# ALight.net
KiCad netlist of a schematic drawn in Altium Designer
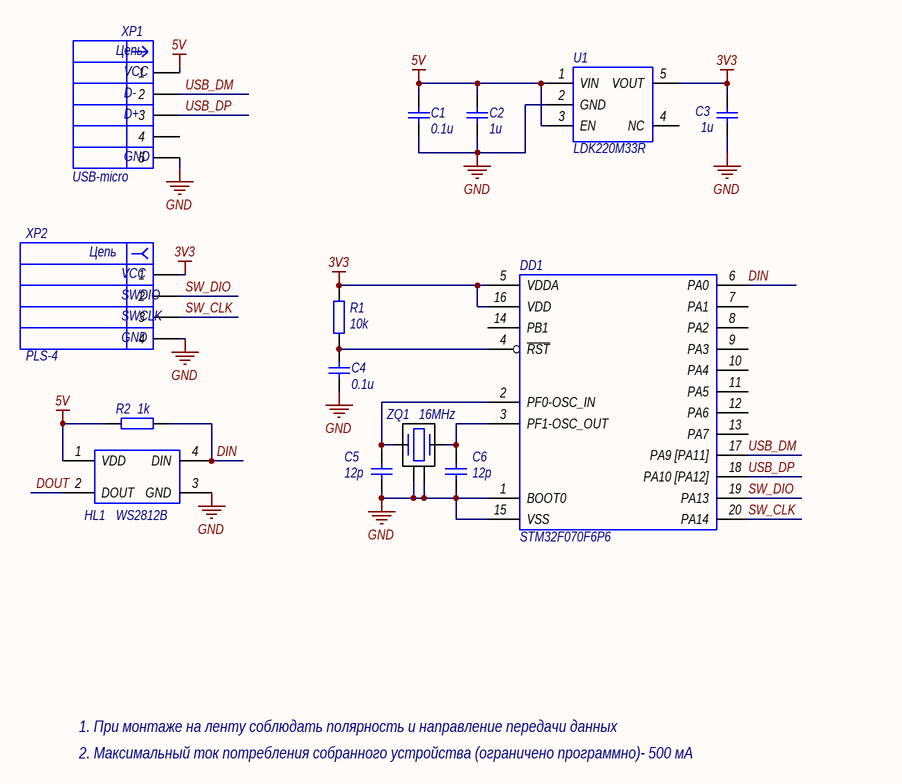
[diagram p0: ALight.SchDoc]

(export (version "E")
  (design (tool "Eeschema 10.0.6"))
  (components
    (comp (ref "C1")
      (value "0.1u")
      (footprint "KDI:CAPACITOR 0603")
      (description "Capacitor")
      (libsource (lib "KDI") (part "SMD-CAP"))
    )
    (comp (ref "C2")
      (value "1u")
      (footprint "KDI:CAPACITOR 0603")
      (description "Capacitor")
      (libsource (lib "KDI") (part "SMD-CAP"))
    )
    (comp (ref "C3")
      (value "1u")
      (footprint "KDI:CAPACITOR 0603")
      (description "Capacitor")
      (libsource (lib "KDI") (part "SMD-CAP"))
    )
    (comp (ref "C4")
      (value "0.1u")
      (footprint "KDI:CAPACITOR 0603")
      (description "Capacitor")
      (libsource (lib "KDI") (part "SMD-CAP"))
    )
    (comp (ref "C5")
      (value "12p")
      (footprint "KDI:CAPACITOR 0603")
      (description "Capacitor")
      (libsource (lib "KDI") (part "SMD-CAP"))
    )
    (comp (ref "C6")
      (value "12p")
      (footprint "KDI:CAPACITOR 0603")
      (description "Capacitor")
      (libsource (lib "KDI") (part "SMD-CAP"))
    )
    (comp (ref "DD1")
      (value "STM32F070F6P6")
      (footprint "TSOP-20")
      (description "Controller")
      (libsource (lib "KDI") (part "STM32F070F6P6"))
    )
    (comp (ref "HL1")
      (value "WS2812B")
      (footprint "LED WS2812")
      (description "LED")
      (libsource (lib "KDI") (part "WS2812B"))
    )
    (comp (ref "R1")
      (value "10k")
      (footprint "RESISTOR 0603")
      (description "Resistor")
      (libsource (lib "KDI") (part "SMD-RES"))
    )
    (comp (ref "R2")
      (value "1k")
      (footprint "RESISTOR 0603")
      (description "Resistor")
      (libsource (lib "KDI") (part "SMD-RES"))
    )
    (comp (ref "U1")
      (value "LDK220M33R")
      (footprint "SOT23-5")
      (description "POWER")
      (libsource (lib "KDI") (part "TPS76333DBVR"))
    )
    (comp (ref "XP1")
      (value "USB-micro")
      (footprint "USB-micro")
      (description "Connector")
      (libsource (lib "KDI") (part "USB-M"))
    )
    (comp (ref "XP2")
      (value "PLS-4")
      (footprint "SWD")
      (description "Connector")
      (libsource (lib "KDI") (part "XP4"))
    )
    (comp (ref "ZQ1")
      (value "16MHz")
      (footprint "SMD0302C4")
      (description "Quartz")
      (libsource (lib "KDI") (part "Quartz"))
    )
  )
  (nets
    (net (code "1") (name "/DIN") (class "Default")
      (node (ref "DD1") (pin "6") (pinfunction "PA0_6") (pintype "passive"))
      (node (ref "HL1") (pin "4") (pinfunction "DIN_4") (pintype "passive"))
      (node (ref "R2") (pin "2") (pinfunction "2_2") (pintype "passive"))
    )
    (net (code "2") (name "/DOUT") (class "Default")
      (node (ref "HL1") (pin "2") (pinfunction "DOUT_2") (pintype "passive"))
    )
    (net (code "3") (name "/SW_CLK") (class "Default")
      (node (ref "DD1") (pin "20") (pinfunction "PA14_20") (pintype "passive"))
      (node (ref "XP2") (pin "3") (pinfunction "3_3") (pintype "passive"))
    )
    (net (code "4") (name "/SW_DIO") (class "Default")
      (node (ref "DD1") (pin "19") (pinfunction "PA13_19") (pintype "passive"))
      (node (ref "XP2") (pin "2") (pinfunction "2_2") (pintype "passive"))
    )
    (net (code "5") (name "/USB_DM") (class "Default")
      (node (ref "DD1") (pin "17") (pinfunction "PA9_[PA11]_17") (pintype "passive"))
      (node (ref "XP1") (pin "2") (pinfunction "2_2") (pintype "passive"))
    )
    (net (code "6") (name "/USB_DP") (class "Default")
      (node (ref "DD1") (pin "18") (pinfunction "PA10_[PA12]_18") (pintype "passive"))
      (node (ref "XP1") (pin "3") (pinfunction "3_3") (pintype "passive"))
    )
    (net (code "7") (name "3V3") (class "Default")
      (node (ref "C3") (pin "1") (pinfunction "1_1") (pintype "passive"))
      (node (ref "DD1") (pin "16") (pinfunction "VDD_16") (pintype "passive"))
      (node (ref "DD1") (pin "5") (pinfunction "VDDA_5") (pintype "passive"))
      (node (ref "R1") (pin "1") (pinfunction "1_1") (pintype "passive"))
      (node (ref "U1") (pin "5") (pinfunction "VOUT_5") (pintype "passive"))
      (node (ref "XP2") (pin "1") (pinfunction "1_1") (pintype "passive"))
    )
    (net (code "8") (name "5V") (class "Default")
      (node (ref "C1") (pin "1") (pinfunction "1_1") (pintype "passive"))
      (node (ref "C2") (pin "1") (pinfunction "1_1") (pintype "passive"))
      (node (ref "HL1") (pin "1") (pinfunction "VDD_1") (pintype "passive"))
      (node (ref "R2") (pin "1") (pinfunction "1_1") (pintype "passive"))
      (node (ref "U1") (pin "1") (pinfunction "VIN_1") (pintype "passive"))
      (node (ref "U1") (pin "3") (pinfunction "EN_3") (pintype "passive"))
      (node (ref "XP1") (pin "1") (pinfunction "1_1") (pintype "passive"))
    )
    (net (code "9") (name "GND") (class "Default")
      (node (ref "C1") (pin "2") (pinfunction "2_2") (pintype "passive"))
      (node (ref "C2") (pin "2") (pinfunction "2_2") (pintype "passive"))
      (node (ref "C3") (pin "2") (pinfunction "2_2") (pintype "passive"))
      (node (ref "C4") (pin "2") (pinfunction "2_2") (pintype "passive"))
      (node (ref "C5") (pin "1") (pinfunction "1_1") (pintype "passive"))
      (node (ref "C6") (pin "1") (pinfunction "1_1") (pintype "passive"))
      (node (ref "DD1") (pin "1") (pinfunction "BOOT0_1") (pintype "passive"))
      (node (ref "DD1") (pin "15") (pinfunction "VSS_15") (pintype "passive"))
      (node (ref "HL1") (pin "3") (pinfunction "GND_3") (pintype "passive"))
      (node (ref "U1") (pin "2") (pinfunction "GND_2") (pintype "passive"))
      (node (ref "XP1") (pin "5") (pinfunction "5_5") (pintype "passive"))
      (node (ref "XP2") (pin "4") (pinfunction "4_4") (pintype "passive"))
      (node (ref "ZQ1") (pin "2") (pinfunction "5_2") (pintype "passive"))
      (node (ref "ZQ1") (pin "4") (pinfunction "4_4") (pintype "passive"))
    )
    (net (code "10") (name "Net-(DD1-PF0-OSC_IN)") (class "Default")
      (node (ref "C5") (pin "2") (pinfunction "2_2") (pintype "passive"))
      (node (ref "DD1") (pin "2") (pinfunction "PF0-OSC_IN_2") (pintype "passive"))
      (node (ref "ZQ1") (pin "1") (pinfunction "1_1") (pintype "passive"))
    )
    (net (code "11") (name "Net-(DD1-PF1-OSC_OUT)") (class "Default")
      (node (ref "C6") (pin "2") (pinfunction "2_2") (pintype "passive"))
      (node (ref "DD1") (pin "3") (pinfunction "PF1-OSC_OUT_3") (pintype "passive"))
      (node (ref "ZQ1") (pin "3") (pinfunction "3_3") (pintype "passive"))
    )
    (net (code "12") (name "Net-(DD1-~{RST})") (class "Default")
      (node (ref "C4") (pin "1") (pinfunction "1_1") (pintype "passive"))
      (node (ref "DD1") (pin "4") (pinfunction "~{RST}_4") (pintype "passive"))
      (node (ref "R1") (pin "2") (pinfunction "2_2") (pintype "passive"))
    )
    (net (code "13") (name "unconnected-(DD1-PA1-Pad7)") (class "Default")
      (node (ref "DD1") (pin "7") (pinfunction "PA1_7") (pintype "passive"))
    )
    (net (code "14") (name "unconnected-(DD1-PA2-Pad8)") (class "Default")
      (node (ref "DD1") (pin "8") (pinfunction "PA2_8") (pintype "passive"))
    )
    (net (code "15") (name "unconnected-(DD1-PA3-Pad9)") (class "Default")
      (node (ref "DD1") (pin "9") (pinfunction "PA3_9") (pintype "passive"))
    )
    (net (code "16") (name "unconnected-(DD1-PA4-Pad10)") (class "Default")
      (node (ref "DD1") (pin "10") (pinfunction "PA4_10") (pintype "passive"))
    )
    (net (code "17") (name "unconnected-(DD1-PA5-Pad11)") (class "Default")
      (node (ref "DD1") (pin "11") (pinfunction "PA5_11") (pintype "passive"))
    )
    (net (code "18") (name "unconnected-(DD1-PA6-Pad12)") (class "Default")
      (node (ref "DD1") (pin "12") (pinfunction "PA6_12") (pintype "passive"))
    )
    (net (code "19") (name "unconnected-(DD1-PA7-Pad13)") (class "Default")
      (node (ref "DD1") (pin "13") (pinfunction "PA7_13") (pintype "passive"))
    )
    (net (code "20") (name "unconnected-(DD1-PB1-Pad14)") (class "Default")
      (node (ref "DD1") (pin "14") (pinfunction "PB1_14") (pintype "passive"))
    )
    (net (code "21") (name "unconnected-(U1-NC-Pad4)") (class "Default")
      (node (ref "U1") (pin "4") (pinfunction "NC_4") (pintype "passive"))
    )
    (net (code "22") (name "unconnected-(XP1-Pad4)") (class "Default")
      (node (ref "XP1") (pin "4") (pinfunction "4_4") (pintype "passive"))
    )
  )
)
